# toggleswitch.net
KiCad netlist of a schematic drawn in EAGLE
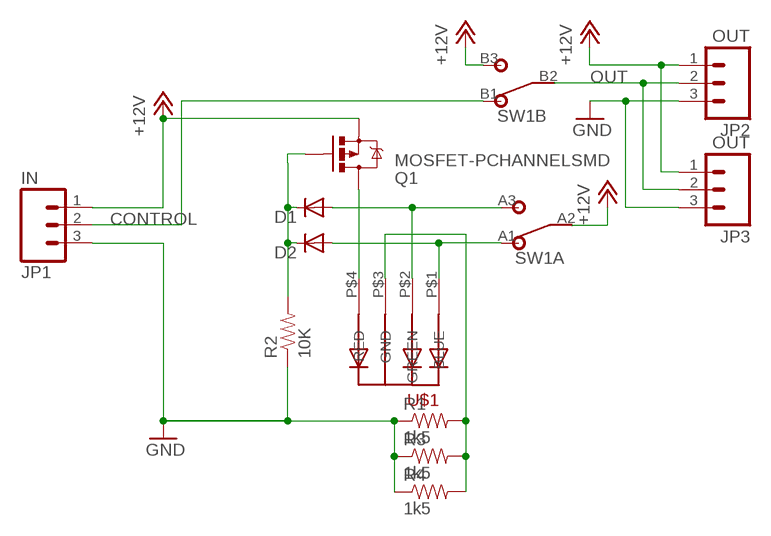
[diagram p0: schematic, sheet 1]

(export (version "E")
  (design (tool "Eeschema 10.0.6"))
  (components
    (comp (ref "D1")
      (value "DIODE-MINIMELF")
      (footprint "eagle-import:MINIMELF")
      (libsource (lib "eagle-import") (part "DIODE-MINIMELF"))
    )
    (comp (ref "D2")
      (value "DIODE-MINIMELF")
      (footprint "eagle-import:MINIMELF")
      (libsource (lib "eagle-import") (part "DIODE-MINIMELF"))
    )
    (comp (ref "JP1")
      (value "IN")
      (footprint "eagle-import:MOLEX-1X3_LOCK")
      (libsource (lib "eagle-import") (part "M03POLAR_LOCK"))
    )
    (comp (ref "JP2")
      (value "OUT")
      (footprint "eagle-import:MOLEX-1X3_LOCK")
      (libsource (lib "eagle-import") (part "M03POLAR_LOCK"))
    )
    (comp (ref "JP3")
      (value "OUT")
      (footprint "eagle-import:MOLEX-1X3_LOCK")
      (libsource (lib "eagle-import") (part "M03POLAR_LOCK"))
    )
    (comp (ref "Q1")
      (value "MOSFET-PCHANNELSMD")
      (footprint "eagle-import:SOT23-3")
      (libsource (lib "eagle-import") (part "MOSFET-PCHANNELSMD"))
    )
    (comp (ref "R1")
      (value "1k5")
      (footprint "eagle-import:0603-RES")
      (libsource (lib "eagle-import") (part "RESISTOR0603-RES"))
    )
    (comp (ref "R2")
      (value "10K")
      (footprint "eagle-import:0603-RES")
      (libsource (lib "eagle-import") (part "RESISTOR0603-RES"))
    )
    (comp (ref "R3")
      (value "1k5")
      (footprint "eagle-import:0603-RES")
      (libsource (lib "eagle-import") (part "RESISTOR0603-RES"))
    )
    (comp (ref "R4")
      (value "1k5")
      (footprint "eagle-import:0603-RES")
      (libsource (lib "eagle-import") (part "RESISTOR0603-RES"))
    )
    (comp (ref "SW1")
      (value "DPDT")
      (footprint "eagle-import:DPDT")
      (libsource (lib "eagle-import") (part "DPDT"))
    )
    (comp (ref "U$1")
      (value "5MMRGBLED")
      (footprint "eagle-import:LED5MMRGB")
      (libsource (lib "eagle-import") (part "5MMRGBLED"))
    )
  )
  (nets
    (net (code "1") (name "+12V") (class "Default")
      (node (ref "JP1") (pin "1") (pinfunction "1_1") (pintype "passive"))
      (node (ref "JP2") (pin "1") (pinfunction "1_1") (pintype "passive"))
      (node (ref "JP3") (pin "1") (pinfunction "1_1") (pintype "passive"))
      (node (ref "Q1") (pin "2") (pinfunction "S_2") (pintype "passive"))
      (node (ref "SW1") (pin "A2") (pinfunction "2_A2") (pintype "passive"))
      (node (ref "SW1") (pin "B3") (pinfunction "3_B3") (pintype "passive"))
    )
    (net (code "2") (name "/CONTROL") (class "Default")
      (node (ref "JP1") (pin "2") (pinfunction "2_2") (pintype "passive"))
      (node (ref "SW1") (pin "B1") (pinfunction "1_B1") (pintype "passive"))
    )
    (net (code "3") (name "/OUT") (class "Default")
      (node (ref "JP2") (pin "2") (pinfunction "2_2") (pintype "passive"))
      (node (ref "JP3") (pin "2") (pinfunction "2_2") (pintype "passive"))
      (node (ref "SW1") (pin "B2") (pinfunction "2_B2") (pintype "passive"))
    )
    (net (code "4") (name "GND") (class "Default")
      (node (ref "JP1") (pin "3") (pinfunction "3_3") (pintype "passive"))
      (node (ref "JP2") (pin "3") (pinfunction "3_3") (pintype "passive"))
      (node (ref "JP3") (pin "3") (pinfunction "3_3") (pintype "passive"))
      (node (ref "R1") (pin "1") (pinfunction "1_1") (pintype "passive"))
      (node (ref "R2") (pin "1") (pinfunction "1_1") (pintype "passive"))
      (node (ref "R3") (pin "1") (pinfunction "1_1") (pintype "passive"))
      (node (ref "R4") (pin "1") (pinfunction "1_1") (pintype "passive"))
    )
    (net (code "5") (name "Net-(Q1-D)") (class "Default")
      (node (ref "Q1") (pin "3") (pinfunction "D_3") (pintype "passive"))
      (node (ref "U$1") (pin "P$4") (pinfunction "RED_P$4") (pintype "bidirectional"))
    )
    (net (code "6") (name "Net-(Q1-G)") (class "Default")
      (node (ref "D1") (pin "C") (pinfunction "C_C") (pintype "passive"))
      (node (ref "D2") (pin "C") (pinfunction "C_C") (pintype "passive"))
      (node (ref "Q1") (pin "1") (pinfunction "G_1") (pintype "passive"))
      (node (ref "R2") (pin "2") (pinfunction "2_2") (pintype "passive"))
    )
    (net (code "7") (name "Net-(SW1A-1)") (class "Default")
      (node (ref "D2") (pin "A") (pinfunction "A_A") (pintype "passive"))
      (node (ref "SW1") (pin "A1") (pinfunction "1_A1") (pintype "passive"))
      (node (ref "U$1") (pin "P$1") (pinfunction "BLUE_P$1") (pintype "bidirectional"))
    )
    (net (code "8") (name "Net-(SW1A-3)") (class "Default")
      (node (ref "D1") (pin "A") (pinfunction "A_A") (pintype "passive"))
      (node (ref "SW1") (pin "A3") (pinfunction "3_A3") (pintype "passive"))
      (node (ref "U$1") (pin "P$2") (pinfunction "GREEN_P$2") (pintype "bidirectional"))
    )
    (net (code "9") (name "Net-(U$1-GND)") (class "Default")
      (node (ref "R1") (pin "2") (pinfunction "2_2") (pintype "passive"))
      (node (ref "R3") (pin "2") (pinfunction "2_2") (pintype "passive"))
      (node (ref "R4") (pin "2") (pinfunction "2_2") (pintype "passive"))
      (node (ref "U$1") (pin "P$3") (pinfunction "GND_P$3") (pintype "bidirectional"))
    )
  )
)
